# Shematic_Hall_Sensor_App.net
KiCad netlist of a schematic drawn in Altium Designer
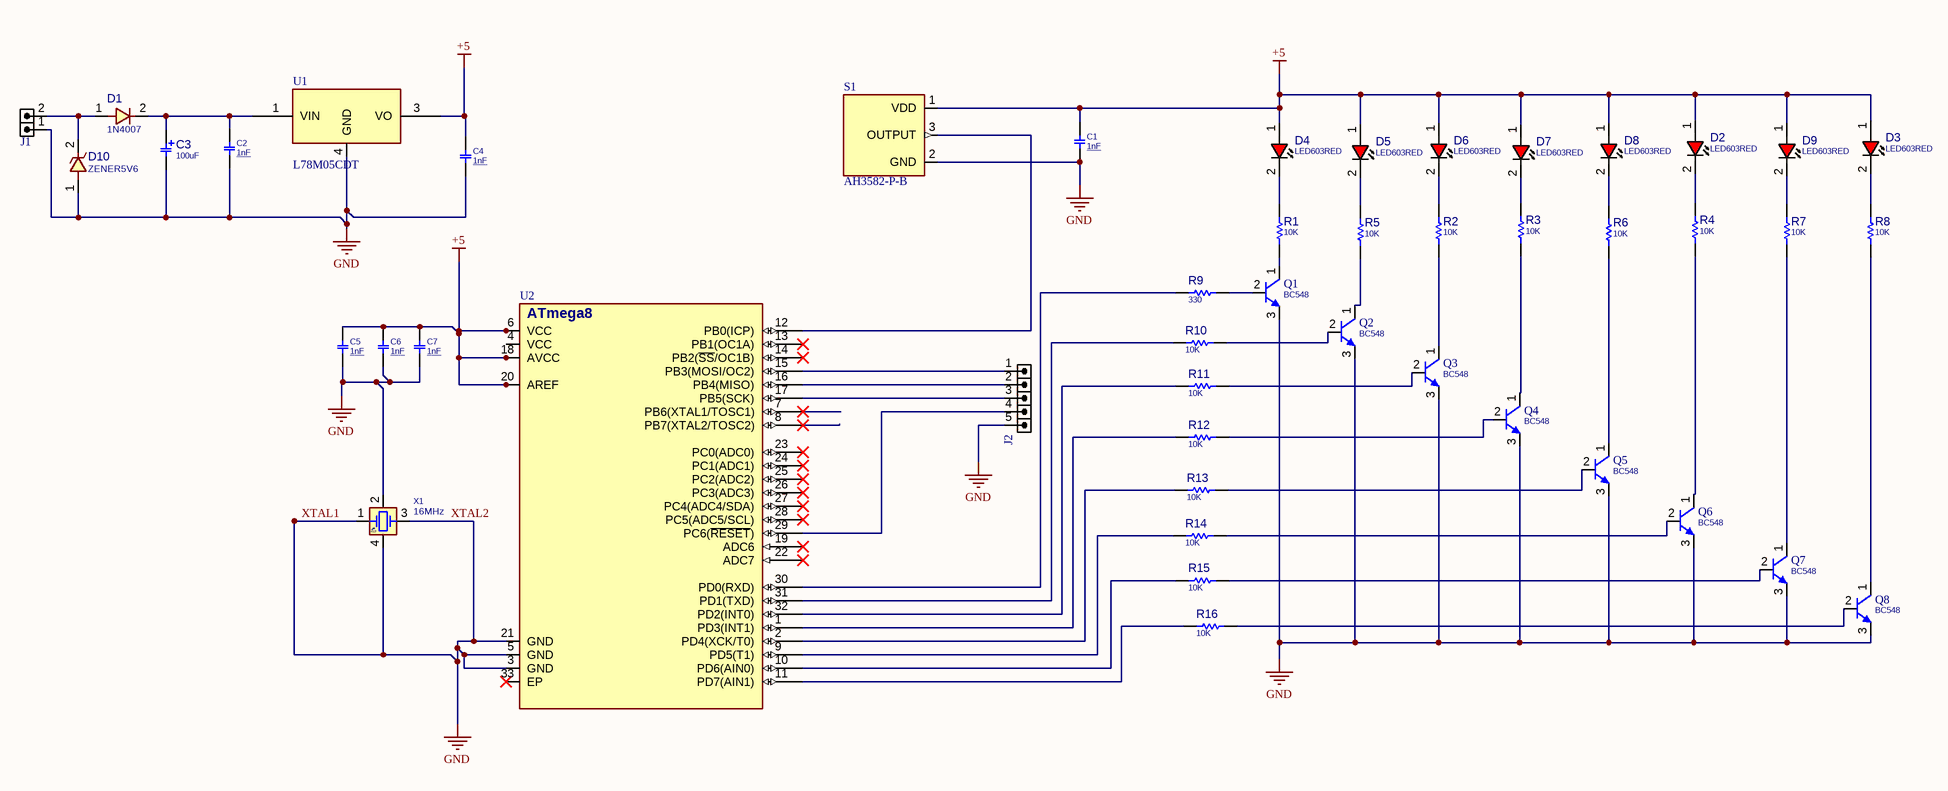
[diagram p0: Shematic_Hall_Sensor_App.SchDoc]

(export (version "E")
  (design (tool "Eeschema 10.0.6"))
  (components
    (comp (ref "C1")
      (value "1nF")
      (footprint "C0402")
      (description "CAP, MLCC, 1nF, 50V, C0G, 10%, 0402")
      (fields (field (name "MANF_P#") "MANF_PART#") (field (name "MANF") "Murata"))
      (libsource (lib "passive_smd") (part "CAP_SMD_MLCC"))
    )
    (comp (ref "C2")
      (value "1nF")
      (footprint "C0402")
      (description "CAP, MLCC, 1nF, 50V, C0G, 10%, 0402")
      (fields (field (name "MANF_P#") "MANF_PART#") (field (name "MANF") "Murata"))
      (libsource (lib "passive_smd") (part "CAP_SMD_MLCC"))
    )
    (comp (ref "C3")
      (value "100uF")
      (footprint "C_EL_8")
      (description "CAP, THD, ELEC,")
      (fields (field (name "MANF_P#") "MANF_PART#") (field (name "MANF") "MANF"))
      (libsource (lib "passive_smd") (part "CAP_SMD_EL"))
    )
    (comp (ref "C4")
      (value "1nF")
      (footprint "C0402")
      (description "CAP, MLCC, 1nF, 50V, C0G, 10%, 0402")
      (fields (field (name "MANF_P#") "MANF_PART#") (field (name "MANF") "Murata"))
      (libsource (lib "passive_smd") (part "CAP_SMD_MLCC"))
    )
    (comp (ref "C5")
      (value "1nF")
      (footprint "C0402")
      (description "CAP, MLCC, 1nF, 50V, C0G, 10%, 0402")
      (fields (field (name "MANF_P#") "MANF_PART#") (field (name "MANF") "Murata"))
      (libsource (lib "passive_smd") (part "CAP_SMD_MLCC"))
    )
    (comp (ref "C6")
      (value "1nF")
      (footprint "C0402")
      (description "CAP, MLCC, 1nF, 50V, C0G, 10%, 0402")
      (fields (field (name "MANF_P#") "MANF_PART#") (field (name "MANF") "Murata"))
      (libsource (lib "passive_smd") (part "CAP_SMD_MLCC"))
    )
    (comp (ref "C7")
      (value "1nF")
      (footprint "C0402")
      (description "CAP, MLCC, 1nF, 50V, C0G, 10%, 0402")
      (fields (field (name "MANF_P#") "MANF_PART#") (field (name "MANF") "Murata"))
      (libsource (lib "passive_smd") (part "CAP_SMD_MLCC"))
    )
    (comp (ref "D1")
      (value "1N4007")
      (footprint "D_SMA")
      (description "DIODE, GENERAL PURPOSE, 1000V/1A")
      (fields (field (name "MANF") "Kingtronics") (field (name "MANF_P#") "M7"))
      (libsource (lib "diode") (part "DIODE_SMD_1N4007"))
    )
    (comp (ref "D2")
      (value "LED603RED")
      (footprint "LED0603RED")
      (description "LED, SMD, 0603, RED")
      (fields (field (name "MANF") "MANF") (field (name "MANF_P#") "MANF_PART#"))
      (libsource (lib "led(diode)") (part "LED_SMD_0603_RED"))
    )
    (comp (ref "D3")
      (value "LED603RED")
      (footprint "LED0603RED")
      (description "LED, SMD, 0603, RED")
      (fields (field (name "MANF") "MANF") (field (name "MANF_P#") "MANF_PART#"))
      (libsource (lib "led(diode)") (part "LED_SMD_0603_RED"))
    )
    (comp (ref "D4")
      (value "LED603RED")
      (footprint "LED0603RED")
      (description "LED, SMD, 0603, RED")
      (fields (field (name "MANF") "MANF") (field (name "MANF_P#") "MANF_PART#"))
      (libsource (lib "led(diode)") (part "LED_SMD_0603_RED"))
    )
    (comp (ref "D5")
      (value "LED603RED")
      (footprint "LED0603RED")
      (description "LED, SMD, 0603, RED")
      (fields (field (name "MANF") "MANF") (field (name "MANF_P#") "MANF_PART#"))
      (libsource (lib "led(diode)") (part "LED_SMD_0603_RED"))
    )
    (comp (ref "D6")
      (value "LED603RED")
      (footprint "LED0603RED")
      (description "LED, SMD, 0603, RED")
      (fields (field (name "MANF") "MANF") (field (name "MANF_P#") "MANF_PART#"))
      (libsource (lib "led(diode)") (part "LED_SMD_0603_RED"))
    )
    (comp (ref "D7")
      (value "LED603RED")
      (footprint "LED0603RED")
      (description "LED, SMD, 0603, RED")
      (fields (field (name "MANF") "MANF") (field (name "MANF_P#") "MANF_PART#"))
      (libsource (lib "led(diode)") (part "LED_SMD_0603_RED"))
    )
    (comp (ref "D8")
      (value "LED603RED")
      (footprint "LED0603RED")
      (description "LED, SMD, 0603, RED")
      (fields (field (name "MANF") "MANF") (field (name "MANF_P#") "MANF_PART#"))
      (libsource (lib "led(diode)") (part "LED_SMD_0603_RED"))
    )
    (comp (ref "D9")
      (value "LED603RED")
      (footprint "LED0603RED")
      (description "LED, SMD, 0603, RED")
      (fields (field (name "MANF") "MANF") (field (name "MANF_P#") "MANF_PART#"))
      (libsource (lib "led(diode)") (part "LED_SMD_0603_RED"))
    )
    (comp (ref "D10")
      (value "ZENER5V6")
      (footprint "D_SOD123W")
      (description "DIODE, ZENER, 1W, 5.1V")
      (fields (field (name "MANF") "Diodes") (field (name "MANF_P#") "DFLZ5V6-7"))
      (libsource (lib "diode") (part "DIODE_SMD_ZENER_DFLZ5V6"))
    )
    (comp (ref "J1")
      (value "HDRM2")
      (footprint "HDR_M_1X2")
      (description "CONN, HEADER, Male, pitch: 2.54mm, 2POS")
      (libsource (lib "conn_header_2.54_st") (part "HDR_M_1X2"))
    )
    (comp (ref "J2")
      (value "HDR1X5")
      (footprint "HDR_M_1X5")
      (description "CONN, HEADER, Male, pitch: 2.54mm, 5POS")
      (libsource (lib "conn_header_2.54_st") (part "HDR_M_1X5"))
    )
    (comp (ref "Q1")
      (value "BC548")
      (footprint "TO92_3")
      (description "BJT, NPN, 30v, 0.1A, THD, TO92")
      (fields (field (name "MANF") "FAIRCHILD"))
      (libsource (lib "transistor_bjt") (part "NPN_BC548_TO92"))
    )
    (comp (ref "Q2")
      (value "BC548")
      (footprint "TO92_3")
      (description "BJT, NPN, 30v, 0.1A, THD, TO92")
      (fields (field (name "MANF") "FAIRCHILD"))
      (libsource (lib "transistor_bjt") (part "NPN_BC548_TO92"))
    )
    (comp (ref "Q3")
      (value "BC548")
      (footprint "TO92_3")
      (description "BJT, NPN, 30v, 0.1A, THD, TO92")
      (fields (field (name "MANF") "FAIRCHILD"))
      (libsource (lib "transistor_bjt") (part "NPN_BC548_TO92"))
    )
    (comp (ref "Q4")
      (value "BC548")
      (footprint "TO92_3")
      (description "BJT, NPN, 30v, 0.1A, THD, TO92")
      (fields (field (name "MANF") "FAIRCHILD"))
      (libsource (lib "transistor_bjt") (part "NPN_BC548_TO92"))
    )
    (comp (ref "Q5")
      (value "BC548")
      (footprint "TO92_3")
      (description "BJT, NPN, 30v, 0.1A, THD, TO92")
      (fields (field (name "MANF") "FAIRCHILD"))
      (libsource (lib "transistor_bjt") (part "NPN_BC548_TO92"))
    )
    (comp (ref "Q6")
      (value "BC548")
      (footprint "TO92_3")
      (description "BJT, NPN, 30v, 0.1A, THD, TO92")
      (fields (field (name "MANF") "FAIRCHILD"))
      (libsource (lib "transistor_bjt") (part "NPN_BC548_TO92"))
    )
    (comp (ref "Q7")
      (value "BC548")
      (footprint "TO92_3")
      (description "BJT, NPN, 30v, 0.1A, THD, TO92")
      (fields (field (name "MANF") "FAIRCHILD"))
      (libsource (lib "transistor_bjt") (part "NPN_BC548_TO92"))
    )
    (comp (ref "Q8")
      (value "BC548")
      (footprint "TO92_3")
      (description "BJT, NPN, 30v, 0.1A, THD, TO92")
      (fields (field (name "MANF") "FAIRCHILD"))
      (libsource (lib "transistor_bjt") (part "NPN_BC548_TO92"))
    )
    (comp (ref "R1")
      (value "10K")
      (footprint "R0603")
      (description "RESISTOR, SMD")
      (libsource (lib "passive_smd") (part "RES_SMD_0603"))
    )
    (comp (ref "R2")
      (value "10K")
      (footprint "R0603")
      (description "RESISTOR, SMD")
      (libsource (lib "passive_smd") (part "RES_SMD_0603"))
    )
    (comp (ref "R3")
      (value "10K")
      (footprint "R0603")
      (description "RESISTOR, SMD")
      (libsource (lib "passive_smd") (part "RES_SMD_0603"))
    )
    (comp (ref "R4")
      (value "10K")
      (footprint "R0603")
      (description "RESISTOR, SMD")
      (libsource (lib "passive_smd") (part "RES_SMD_0603"))
    )
    (comp (ref "R5")
      (value "10K")
      (footprint "R0603")
      (description "RESISTOR, SMD")
      (libsource (lib "passive_smd") (part "RES_SMD_0603"))
    )
    (comp (ref "R6")
      (value "10K")
      (footprint "R0603")
      (description "RESISTOR, SMD")
      (libsource (lib "passive_smd") (part "RES_SMD_0603"))
    )
    (comp (ref "R7")
      (value "10K")
      (footprint "R0603")
      (description "RESISTOR, SMD")
      (libsource (lib "passive_smd") (part "RES_SMD_0603"))
    )
    (comp (ref "R8")
      (value "10K")
      (footprint "R0603")
      (description "RESISTOR, SMD")
      (libsource (lib "passive_smd") (part "RES_SMD_0603"))
    )
    (comp (ref "R9")
      (value "330")
      (footprint "R0603")
      (description "RESISTOR, SMD")
      (libsource (lib "res_smd_passive") (part "RES_SMD_0603"))
    )
    (comp (ref "R10")
      (value "10K")
      (footprint "R0603")
      (description "RESISTOR, SMD")
      (libsource (lib "passive_smd") (part "RES_SMD_0603"))
    )
    (comp (ref "R11")
      (value "10K")
      (footprint "R0603")
      (description "RESISTOR, SMD")
      (libsource (lib "passive_smd") (part "RES_SMD_0603"))
    )
    (comp (ref "R12")
      (value "10K")
      (footprint "R0603")
      (description "RESISTOR, SMD")
      (libsource (lib "passive_smd") (part "RES_SMD_0603"))
    )
    (comp (ref "R13")
      (value "10K")
      (footprint "R0603")
      (description "RESISTOR, SMD")
      (libsource (lib "passive_smd") (part "RES_SMD_0603"))
    )
    (comp (ref "R14")
      (value "10K")
      (footprint "R0603")
      (description "RESISTOR, SMD")
      (libsource (lib "passive_smd") (part "RES_SMD_0603"))
    )
    (comp (ref "R15")
      (value "10K")
      (footprint "R0603")
      (description "RESISTOR, SMD")
      (libsource (lib "passive_smd") (part "RES_SMD_0603"))
    )
    (comp (ref "R16")
      (value "10K")
      (footprint "R0603")
      (description "RESISTOR, SMD")
      (libsource (lib "passive_smd") (part "RES_SMD_0603"))
    )
    (comp (ref "S1")
      (value "AH3582-P-B")
      (footprint "SIP160W38P127L430H495Q3")
      (description "HALL OMNIPOLAR SWITCH,SIP-3,BULK")
      (libsource (lib "AH3582-P-B") (part "AH3582-P-B"))
    )
    (comp (ref "U1")
      (value "L78M05CDT")
      (footprint "DPAK_3")
      (description "REG, Linear, Fixed, 5v, 0.5A, TO-252")
      (fields (field (name "MANF") "TI, ST, FAIRCHILD, ON, NJR, ROHM, DIODES"))
      (libsource (lib "Regulator Linear 78xx 79xx") (part "VREG_78M05_TO252"))
    )
    (comp (ref "U2")
      (value "ATMEGA8")
      (footprint "QFG80_32")
      (description "MCU, AVR, 8-Bit, 8KB, 1KB RAM, 16MHz")
      (fields (field (name "MANF_P#") "ATMEGA8-16AU") (field (name "MANF") "ATMEL/MICROCHIP"))
      (libsource (lib "MCU 8Bit AVR Mega8-48-88-168-328") (part "ATMEGA8_QFP32"))
    )
    (comp (ref "X1")
      (value "16MHz")
      (footprint "XTL_4_2520")
      (description "Crystal 16MHz")
      (fields (field (name "MANF") "ABRACON") (field (name "MANF_P#") "ABM10W-16.0000MHZ-4-D1X-T3"))
      (libsource (lib "crystal") (part "XTL_4_16MHz_2520"))
    )
  )
  (nets
    (net (code "1") (name "+5") (class "Default")
      (node (ref "C1") (pin "1") (pinfunction "1_1") (pintype "passive"))
      (node (ref "C4") (pin "1") (pinfunction "1_1") (pintype "passive"))
      (node (ref "C5") (pin "1") (pinfunction "1_1") (pintype "passive"))
      (node (ref "C6") (pin "1") (pinfunction "1_1") (pintype "passive"))
      (node (ref "C7") (pin "1") (pinfunction "1_1") (pintype "passive"))
      (node (ref "D2") (pin "1") (pinfunction "ANODE_1") (pintype "passive"))
      (node (ref "D3") (pin "1") (pinfunction "ANODE_1") (pintype "passive"))
      (node (ref "D4") (pin "1") (pinfunction "ANODE_1") (pintype "passive"))
      (node (ref "D5") (pin "1") (pinfunction "ANODE_1") (pintype "passive"))
      (node (ref "D6") (pin "1") (pinfunction "ANODE_1") (pintype "passive"))
      (node (ref "D7") (pin "1") (pinfunction "ANODE_1") (pintype "passive"))
      (node (ref "D8") (pin "1") (pinfunction "ANODE_1") (pintype "passive"))
      (node (ref "D9") (pin "1") (pinfunction "ANODE_1") (pintype "passive"))
      (node (ref "S1") (pin "1") (pinfunction "VDD_1") (pintype "power_in"))
      (node (ref "U1") (pin "3") (pinfunction "VO_3") (pintype "passive"))
      (node (ref "U2") (pin "18") (pinfunction "AVCC_18") (pintype "power_in"))
      (node (ref "U2") (pin "20") (pinfunction "AREF_20") (pintype "passive"))
      (node (ref "U2") (pin "6") (pinfunction "VCC_6") (pintype "power_in"))
    )
    (net (code "2") (name "GND") (class "Default")
      (node (ref "C1") (pin "2") (pinfunction "2_2") (pintype "passive"))
      (node (ref "C2") (pin "2") (pinfunction "2_2") (pintype "passive"))
      (node (ref "C3") (pin "2") (pinfunction "2_2") (pintype "passive"))
      (node (ref "C4") (pin "2") (pinfunction "2_2") (pintype "passive"))
      (node (ref "C5") (pin "2") (pinfunction "2_2") (pintype "passive"))
      (node (ref "C6") (pin "2") (pinfunction "2_2") (pintype "passive"))
      (node (ref "C7") (pin "2") (pinfunction "2_2") (pintype "passive"))
      (node (ref "D10") (pin "1") (pinfunction "1_1") (pintype "passive"))
      (node (ref "J1") (pin "1") (pinfunction "1_1") (pintype "passive"))
      (node (ref "J2") (pin "5") (pinfunction "5_5") (pintype "passive"))
      (node (ref "Q1") (pin "3") (pinfunction "E_3") (pintype "passive"))
      (node (ref "Q2") (pin "3") (pinfunction "E_3") (pintype "passive"))
      (node (ref "Q3") (pin "3") (pinfunction "E_3") (pintype "passive"))
      (node (ref "Q4") (pin "3") (pinfunction "E_3") (pintype "passive"))
      (node (ref "Q5") (pin "3") (pinfunction "E_3") (pintype "passive"))
      (node (ref "Q6") (pin "3") (pinfunction "E_3") (pintype "passive"))
      (node (ref "Q7") (pin "3") (pinfunction "E_3") (pintype "passive"))
      (node (ref "Q8") (pin "3") (pinfunction "E_3") (pintype "passive"))
      (node (ref "S1") (pin "2") (pinfunction "GND_2") (pintype "power_in"))
      (node (ref "U1") (pin "4") (pinfunction "GND_4") (pintype "passive"))
      (node (ref "U2") (pin "21") (pinfunction "GND_21") (pintype "power_in"))
      (node (ref "U2") (pin "3") (pinfunction "GND_3") (pintype "power_in"))
      (node (ref "U2") (pin "5") (pinfunction "GND_5") (pintype "power_in"))
      (node (ref "X1") (pin "1") (pinfunction "1_1") (pintype "passive"))
      (node (ref "X1") (pin "2") (pinfunction "2_2") (pintype "passive"))
      (node (ref "X1") (pin "3") (pinfunction "2_3") (pintype "passive"))
      (node (ref "X1") (pin "4") (pinfunction "4_4") (pintype "passive"))
    )
    (net (code "3") (name "Net-(D1-Pad1)") (class "Default")
      (node (ref "D1") (pin "1") (pinfunction "1_1") (pintype "passive"))
      (node (ref "D10") (pin "2") (pinfunction "2_2") (pintype "passive"))
      (node (ref "J1") (pin "2") (pinfunction "2_2") (pintype "passive"))
    )
    (net (code "4") (name "Net-(D2-CATHODE)") (class "Default")
      (node (ref "D2") (pin "2") (pinfunction "CATHODE_2") (pintype "passive"))
      (node (ref "R4") (pin "2") (pinfunction "2_2") (pintype "passive"))
    )
    (net (code "5") (name "Net-(D3-CATHODE)") (class "Default")
      (node (ref "D3") (pin "2") (pinfunction "CATHODE_2") (pintype "passive"))
      (node (ref "R8") (pin "2") (pinfunction "2_2") (pintype "passive"))
    )
    (net (code "6") (name "Net-(D4-CATHODE)") (class "Default")
      (node (ref "D4") (pin "2") (pinfunction "CATHODE_2") (pintype "passive"))
      (node (ref "R1") (pin "2") (pinfunction "2_2") (pintype "passive"))
    )
    (net (code "7") (name "Net-(D5-CATHODE)") (class "Default")
      (node (ref "D5") (pin "2") (pinfunction "CATHODE_2") (pintype "passive"))
      (node (ref "R5") (pin "2") (pinfunction "2_2") (pintype "passive"))
    )
    (net (code "8") (name "Net-(D6-CATHODE)") (class "Default")
      (node (ref "D6") (pin "2") (pinfunction "CATHODE_2") (pintype "passive"))
      (node (ref "R2") (pin "2") (pinfunction "2_2") (pintype "passive"))
    )
    (net (code "9") (name "Net-(D7-CATHODE)") (class "Default")
      (node (ref "D7") (pin "2") (pinfunction "CATHODE_2") (pintype "passive"))
      (node (ref "R3") (pin "2") (pinfunction "2_2") (pintype "passive"))
    )
    (net (code "10") (name "Net-(D8-CATHODE)") (class "Default")
      (node (ref "D8") (pin "2") (pinfunction "CATHODE_2") (pintype "passive"))
      (node (ref "R6") (pin "2") (pinfunction "2_2") (pintype "passive"))
    )
    (net (code "11") (name "Net-(D9-CATHODE)") (class "Default")
      (node (ref "D9") (pin "2") (pinfunction "CATHODE_2") (pintype "passive"))
      (node (ref "R7") (pin "2") (pinfunction "2_2") (pintype "passive"))
    )
    (net (code "12") (name "Net-(Q1-B)") (class "Default")
      (node (ref "Q1") (pin "2") (pinfunction "B_2") (pintype "passive"))
      (node (ref "R9") (pin "2") (pinfunction "2_2") (pintype "passive"))
    )
    (net (code "13") (name "Net-(Q1-C)") (class "Default")
      (node (ref "Q1") (pin "1") (pinfunction "C_1") (pintype "passive"))
      (node (ref "R1") (pin "1") (pinfunction "1_1") (pintype "passive"))
    )
    (net (code "14") (name "Net-(Q2-B)") (class "Default")
      (node (ref "Q2") (pin "2") (pinfunction "B_2") (pintype "passive"))
      (node (ref "R10") (pin "2") (pinfunction "2_2") (pintype "passive"))
    )
    (net (code "15") (name "Net-(Q2-C)") (class "Default")
      (node (ref "Q2") (pin "1") (pinfunction "C_1") (pintype "passive"))
      (node (ref "R5") (pin "1") (pinfunction "1_1") (pintype "passive"))
    )
    (net (code "16") (name "Net-(Q3-B)") (class "Default")
      (node (ref "Q3") (pin "2") (pinfunction "B_2") (pintype "passive"))
      (node (ref "R11") (pin "2") (pinfunction "2_2") (pintype "passive"))
    )
    (net (code "17") (name "Net-(Q3-C)") (class "Default")
      (node (ref "Q3") (pin "1") (pinfunction "C_1") (pintype "passive"))
      (node (ref "R2") (pin "1") (pinfunction "1_1") (pintype "passive"))
    )
    (net (code "18") (name "Net-(Q4-B)") (class "Default")
      (node (ref "Q4") (pin "2") (pinfunction "B_2") (pintype "passive"))
      (node (ref "R12") (pin "2") (pinfunction "2_2") (pintype "passive"))
    )
    (net (code "19") (name "Net-(Q4-C)") (class "Default")
      (node (ref "Q4") (pin "1") (pinfunction "C_1") (pintype "passive"))
      (node (ref "R3") (pin "1") (pinfunction "1_1") (pintype "passive"))
    )
    (net (code "20") (name "Net-(Q5-B)") (class "Default")
      (node (ref "Q5") (pin "2") (pinfunction "B_2") (pintype "passive"))
      (node (ref "R13") (pin "2") (pinfunction "2_2") (pintype "passive"))
    )
    (net (code "21") (name "Net-(Q5-C)") (class "Default")
      (node (ref "Q5") (pin "1") (pinfunction "C_1") (pintype "passive"))
      (node (ref "R6") (pin "1") (pinfunction "1_1") (pintype "passive"))
    )
    (net (code "22") (name "Net-(Q6-B)") (class "Default")
      (node (ref "Q6") (pin "2") (pinfunction "B_2") (pintype "passive"))
      (node (ref "R14") (pin "2") (pinfunction "2_2") (pintype "passive"))
    )
    (net (code "23") (name "Net-(Q6-C)") (class "Default")
      (node (ref "Q6") (pin "1") (pinfunction "C_1") (pintype "passive"))
      (node (ref "R4") (pin "1") (pinfunction "1_1") (pintype "passive"))
    )
    (net (code "24") (name "Net-(Q7-B)") (class "Default")
      (node (ref "Q7") (pin "2") (pinfunction "B_2") (pintype "passive"))
      (node (ref "R15") (pin "2") (pinfunction "2_2") (pintype "passive"))
    )
    (net (code "25") (name "Net-(Q7-C)") (class "Default")
      (node (ref "Q7") (pin "1") (pinfunction "C_1") (pintype "passive"))
      (node (ref "R7") (pin "1") (pinfunction "1_1") (pintype "passive"))
    )
    (net (code "26") (name "Net-(Q8-B)") (class "Default")
      (node (ref "Q8") (pin "2") (pinfunction "B_2") (pintype "passive"))
      (node (ref "R16") (pin "2") (pinfunction "2_2") (pintype "passive"))
    )
    (net (code "27") (name "Net-(Q8-C)") (class "Default")
      (node (ref "Q8") (pin "1") (pinfunction "C_1") (pintype "passive"))
      (node (ref "R8") (pin "1") (pinfunction "1_1") (pintype "passive"))
    )
    (net (code "28") (name "Net-(S1-OUTPUT)") (class "Default")
      (node (ref "S1") (pin "3") (pinfunction "OUTPUT_3") (pintype "output"))
      (node (ref "U2") (pin "12") (pinfunction "PB0(ICP)_12") (pintype "bidirectional"))
    )
    (net (code "29") (name "Net-(U1-VIN)") (class "Default")
      (node (ref "C2") (pin "1") (pinfunction "1_1") (pintype "passive"))
      (node (ref "C3") (pin "1") (pinfunction "1_1") (pintype "passive"))
      (node (ref "D1") (pin "2") (pinfunction "2_2") (pintype "passive"))
      (node (ref "U1") (pin "1") (pinfunction "VIN_1") (pintype "passive"))
    )
    (net (code "30") (name "Net-(U2-PB3(MOSI{slash}OC2))") (class "Default")
      (node (ref "J2") (pin "1") (pinfunction "1_1") (pintype "passive"))
      (node (ref "U2") (pin "15") (pinfunction "PB3(MOSI/OC2)_15") (pintype "bidirectional"))
    )
    (net (code "31") (name "Net-(U2-PB4(MISO))") (class "Default")
      (node (ref "J2") (pin "2") (pinfunction "2_2") (pintype "passive"))
      (node (ref "U2") (pin "16") (pinfunction "PB4(MISO)_16") (pintype "bidirectional"))
    )
    (net (code "32") (name "Net-(U2-PB5(SCK))") (class "Default")
      (node (ref "J2") (pin "3") (pinfunction "3_3") (pintype "passive"))
      (node (ref "U2") (pin "17") (pinfunction "PB5(SCK)_17") (pintype "bidirectional"))
    )
    (net (code "33") (name "Net-(U2-PC6(~{RESET}))") (class "Default")
      (node (ref "J2") (pin "4") (pinfunction "4_4") (pintype "passive"))
      (node (ref "U2") (pin "29") (pinfunction "PC6(~{RESET})_29") (pintype "bidirectional"))
    )
    (net (code "34") (name "Net-(U2-PD0(RXD))") (class "Default")
      (node (ref "R9") (pin "1") (pinfunction "1_1") (pintype "passive"))
      (node (ref "U2") (pin "30") (pinfunction "PD0(RXD)_30") (pintype "bidirectional"))
    )
    (net (code "35") (name "Net-(U2-PD1(TXD))") (class "Default")
      (node (ref "R10") (pin "1") (pinfunction "1_1") (pintype "passive"))
      (node (ref "U2") (pin "31") (pinfunction "PD1(TXD)_31") (pintype "bidirectional"))
    )
    (net (code "36") (name "Net-(U2-PD2(INT0))") (class "Default")
      (node (ref "R11") (pin "1") (pinfunction "1_1") (pintype "passive"))
      (node (ref "U2") (pin "32") (pinfunction "PD2(INT0)_32") (pintype "bidirectional"))
    )
    (net (code "37") (name "Net-(U2-PD3(INT1))") (class "Default")
      (node (ref "R12") (pin "1") (pinfunction "1_1") (pintype "passive"))
      (node (ref "U2") (pin "1") (pinfunction "PD3(INT1)_1") (pintype "bidirectional"))
    )
    (net (code "38") (name "Net-(U2-PD4(XCK{slash}T0))") (class "Default")
      (node (ref "R13") (pin "1") (pinfunction "1_1") (pintype "passive"))
      (node (ref "U2") (pin "2") (pinfunction "PD4(XCK/T0)_2") (pintype "bidirectional"))
    )
    (net (code "39") (name "Net-(U2-PD5(T1))") (class "Default")
      (node (ref "R14") (pin "1") (pinfunction "1_1") (pintype "passive"))
      (node (ref "U2") (pin "9") (pinfunction "PD5(T1)_9") (pintype "bidirectional"))
    )
    (net (code "40") (name "Net-(U2-PD6(AIN0))") (class "Default")
      (node (ref "R15") (pin "1") (pinfunction "1_1") (pintype "passive"))
      (node (ref "U2") (pin "10") (pinfunction "PD6(AIN0)_10") (pintype "bidirectional"))
    )
    (net (code "41") (name "Net-(U2-PD7(AIN1))") (class "Default")
      (node (ref "R16") (pin "1") (pinfunction "1_1") (pintype "passive"))
      (node (ref "U2") (pin "11") (pinfunction "PD7(AIN1)_11") (pintype "bidirectional"))
    )
    (net (code "42") (name "unconnected-(U2-ADC6-Pad19)") (class "Default")
      (node (ref "U2") (pin "19") (pinfunction "ADC6_19") (pintype "input+no_connect"))
    )
    (net (code "43") (name "unconnected-(U2-ADC7-Pad22)") (class "Default")
      (node (ref "U2") (pin "22") (pinfunction "ADC7_22") (pintype "input+no_connect"))
    )
    (net (code "44") (name "unconnected-(U2-EP-Pad33)") (class "Default")
      (node (ref "U2") (pin "33") (pinfunction "EP_33") (pintype "power_in+no_connect"))
    )
    (net (code "45") (name "unconnected-(U2-PB1(OC1A)-Pad13)") (class "Default")
      (node (ref "U2") (pin "13") (pinfunction "PB1(OC1A)_13") (pintype "bidirectional+no_connect"))
    )
    (net (code "46") (name "unconnected-(U2-PB2(~{SS}{slash}OC1B)-Pad14)") (class "Default")
      (node (ref "U2") (pin "14") (pinfunction "PB2(~{SS}/OC1B)_14") (pintype "bidirectional+no_connect"))
    )
    (net (code "47") (name "unconnected-(U2-PB6(XTAL1{slash}TOSC1)-Pad7)") (class "Default")
      (node (ref "U2") (pin "7") (pinfunction "PB6(XTAL1/TOSC1)_7") (pintype "bidirectional+no_connect"))
    )
    (net (code "48") (name "unconnected-(U2-PB7(XTAL2{slash}TOSC2)-Pad8)") (class "Default")
      (node (ref "U2") (pin "8") (pinfunction "PB7(XTAL2/TOSC2)_8") (pintype "bidirectional+no_connect"))
    )
    (net (code "49") (name "unconnected-(U2-PC0(ADC0)-Pad23)") (class "Default")
      (node (ref "U2") (pin "23") (pinfunction "PC0(ADC0)_23") (pintype "bidirectional+no_connect"))
    )
    (net (code "50") (name "unconnected-(U2-PC1(ADC1)-Pad24)") (class "Default")
      (node (ref "U2") (pin "24") (pinfunction "PC1(ADC1)_24") (pintype "bidirectional+no_connect"))
    )
    (net (code "51") (name "unconnected-(U2-PC2(ADC2)-Pad25)") (class "Default")
      (node (ref "U2") (pin "25") (pinfunction "PC2(ADC2)_25") (pintype "bidirectional+no_connect"))
    )
    (net (code "52") (name "unconnected-(U2-PC3(ADC3)-Pad26)") (class "Default")
      (node (ref "U2") (pin "26") (pinfunction "PC3(ADC3)_26") (pintype "bidirectional+no_connect"))
    )
    (net (code "53") (name "unconnected-(U2-PC4(ADC4{slash}SDA)-Pad27)") (class "Default")
      (node (ref "U2") (pin "27") (pinfunction "PC4(ADC4/SDA)_27") (pintype "bidirectional+no_connect"))
    )
    (net (code "54") (name "unconnected-(U2-PC5(ADC5{slash}SCL)-Pad28)") (class "Default")
      (node (ref "U2") (pin "28") (pinfunction "PC5(ADC5/SCL)_28") (pintype "bidirectional+no_connect"))
    )
    (net (code "55") (name "unconnected-(U2-VCC-Pad4)") (class "Default")
      (node (ref "U2") (pin "4") (pinfunction "VCC_4") (pintype "power_in"))
    )
  )
)
